# Output_Power_Distro.net
KiCad netlist of a schematic drawn in EAGLE
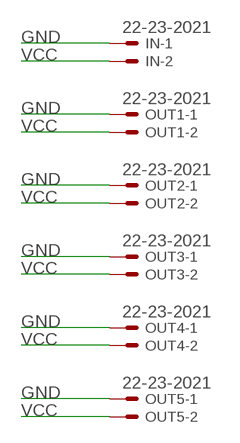
[diagram p0: schematic, sheet 1]

(export (version "E")
  (design (tool "Eeschema 10.0.6"))
  (components
    (comp (ref "IN")
      (value "22-23-2021")
      (footprint "eagle-import:22-23-2021")
      (fields (field (name "MF") "MOLEX"))
      (libsource (lib "eagle-import") (part "22-23-2021"))
    )
    (comp (ref "OUT1")
      (value "22-23-2021")
      (footprint "eagle-import:22-23-2021")
      (fields (field (name "MF") "MOLEX"))
      (libsource (lib "eagle-import") (part "22-23-2021"))
    )
    (comp (ref "OUT2")
      (value "22-23-2021")
      (footprint "eagle-import:22-23-2021")
      (fields (field (name "MF") "MOLEX"))
      (libsource (lib "eagle-import") (part "22-23-2021"))
    )
    (comp (ref "OUT3")
      (value "22-23-2021")
      (footprint "eagle-import:22-23-2021")
      (fields (field (name "MF") "MOLEX"))
      (libsource (lib "eagle-import") (part "22-23-2021"))
    )
    (comp (ref "OUT4")
      (value "22-23-2021")
      (footprint "eagle-import:22-23-2021")
      (fields (field (name "MF") "MOLEX"))
      (libsource (lib "eagle-import") (part "22-23-2021"))
    )
    (comp (ref "OUT5")
      (value "22-23-2021")
      (footprint "eagle-import:22-23-2021")
      (fields (field (name "MF") "MOLEX"))
      (libsource (lib "eagle-import") (part "22-23-2021"))
    )
  )
  (nets
    (net (code "1") (name "/GND") (class "Default")
      (node (ref "IN") (pin "1") (pinfunction "S_1") (pintype "passive"))
      (node (ref "OUT1") (pin "1") (pinfunction "S_1") (pintype "passive"))
      (node (ref "OUT2") (pin "1") (pinfunction "S_1") (pintype "passive"))
      (node (ref "OUT3") (pin "1") (pinfunction "S_1") (pintype "passive"))
      (node (ref "OUT4") (pin "1") (pinfunction "S_1") (pintype "passive"))
      (node (ref "OUT5") (pin "1") (pinfunction "S_1") (pintype "passive"))
    )
    (net (code "2") (name "/VCC") (class "Default")
      (node (ref "IN") (pin "2") (pinfunction "S_2") (pintype "passive"))
      (node (ref "OUT1") (pin "2") (pinfunction "S_2") (pintype "passive"))
      (node (ref "OUT2") (pin "2") (pinfunction "S_2") (pintype "passive"))
      (node (ref "OUT3") (pin "2") (pinfunction "S_2") (pintype "passive"))
      (node (ref "OUT4") (pin "2") (pinfunction "S_2") (pintype "passive"))
      (node (ref "OUT5") (pin "2") (pinfunction "S_2") (pintype "passive"))
    )
  )
)
